# CalcSchematic.net
KiCad netlist of a schematic drawn in EAGLE
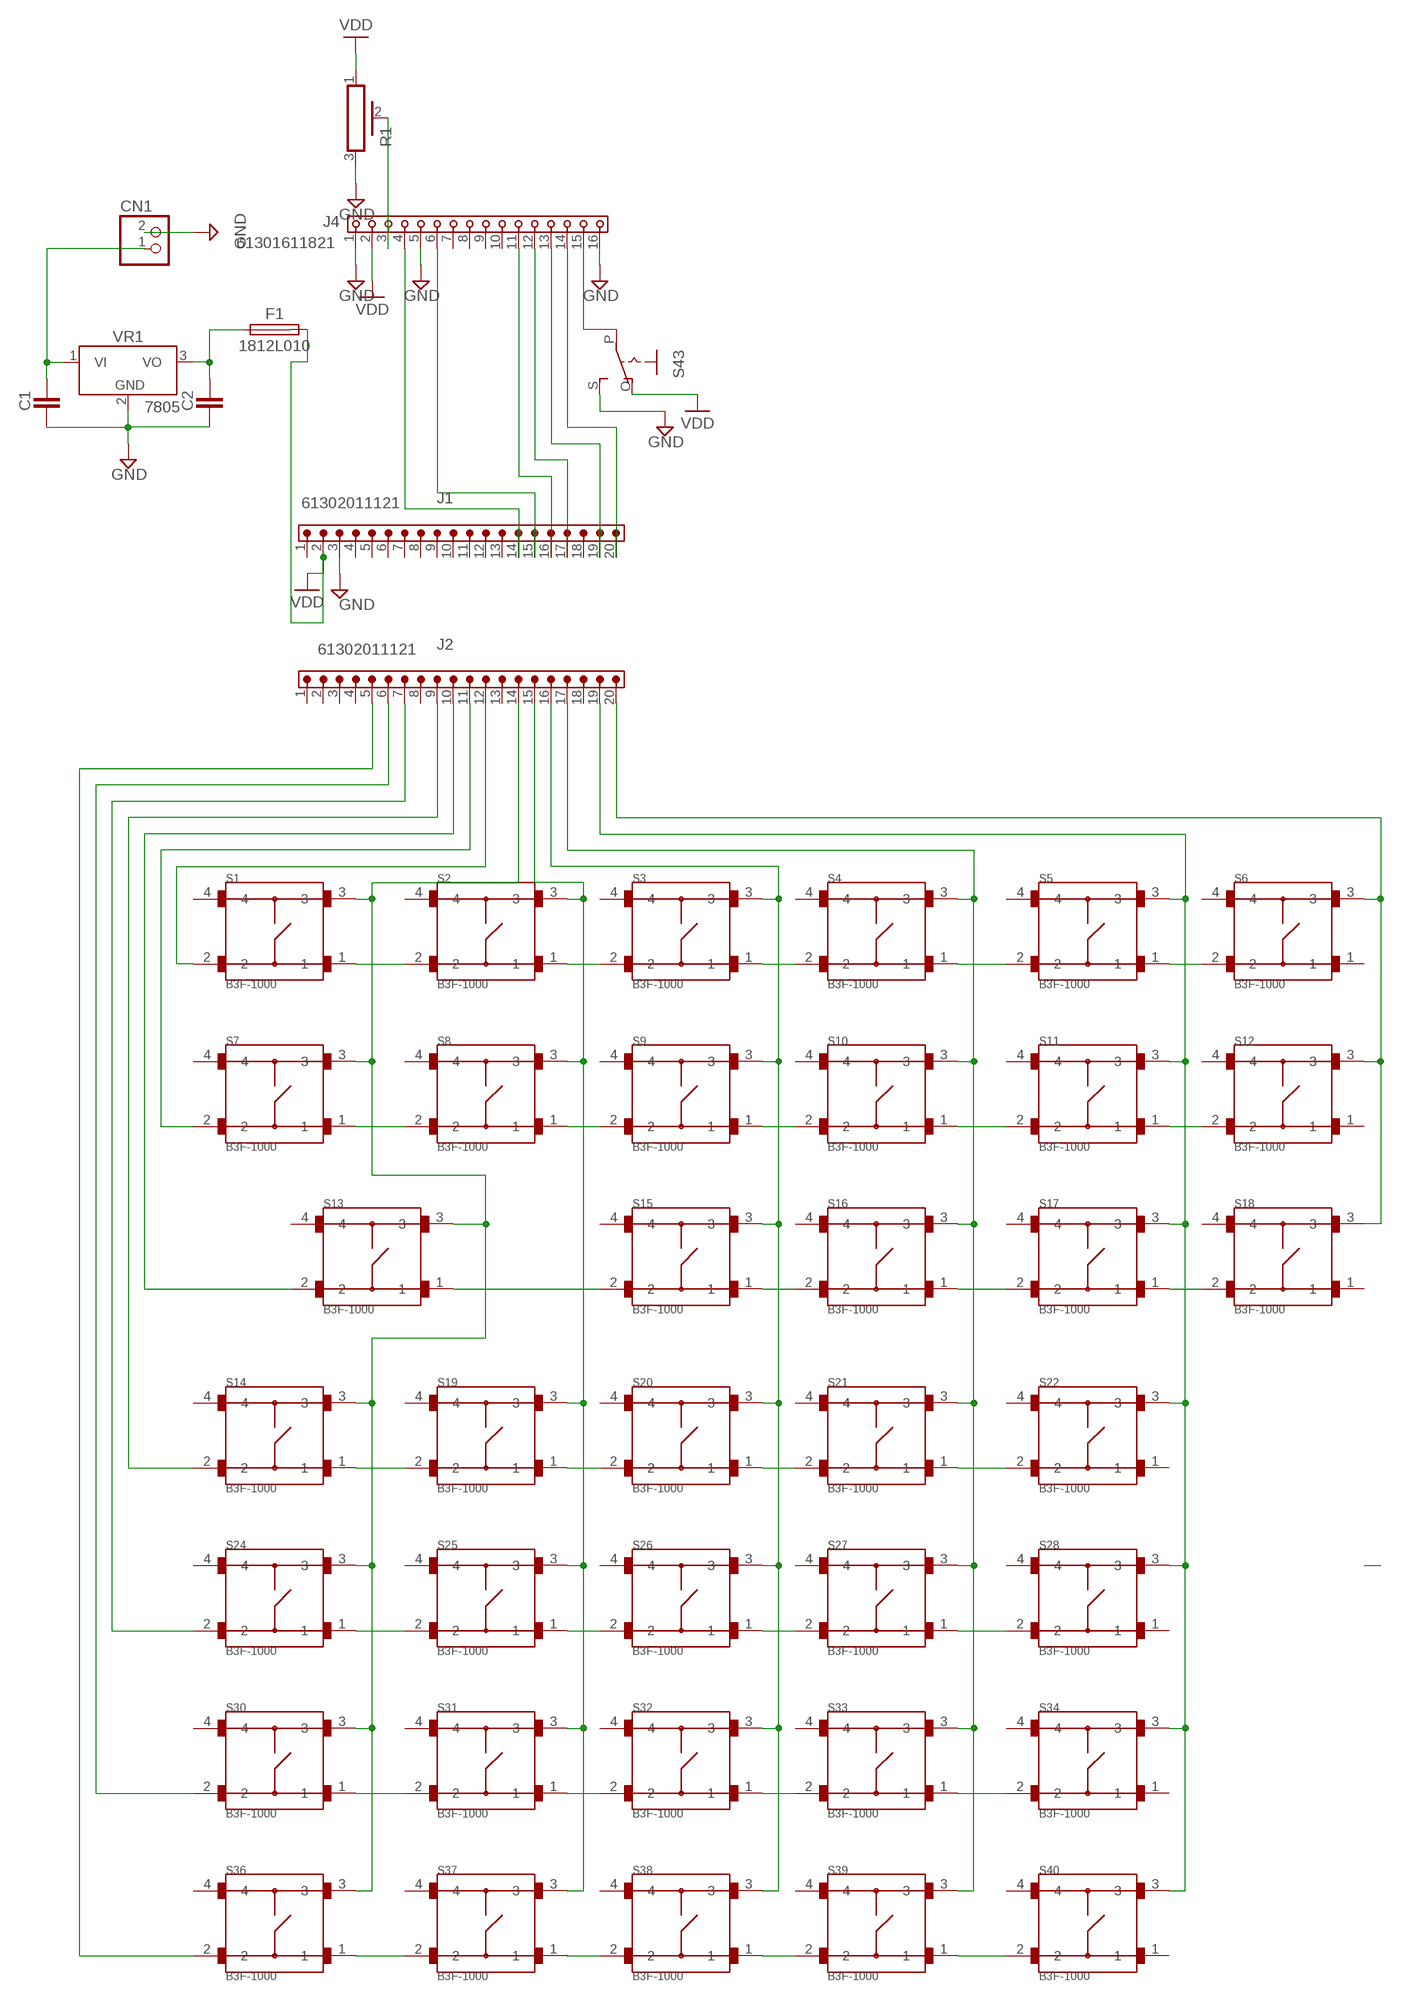
[diagram p0: schematic, sheet 1]

(export (version "E")
  (design (tool "Eeschema 10.0.6"))
  (components
    (comp (ref "C1")
      (value "CAPACITOR_CHIP-1206(3216-METRIC)")
      (footprint "eagle-import:CAPC3216X135")
      (libsource (lib "eagle-import") (part "CAPACITORCHIP-1206(3216-METRIC)_"))
    )
    (comp (ref "C2")
      (value "CAPACITOR_CHIP-1206(3216-METRIC)")
      (footprint "eagle-import:CAPC3216X135")
      (libsource (lib "eagle-import") (part "CAPACITORCHIP-1206(3216-METRIC)_"))
    )
    (comp (ref "CN1")
      (value "JST_2PIN-THM")
      (footprint "eagle-import:JST-PH-2-THM")
      (libsource (lib "eagle-import") (part "JST_2PIN-THM"))
    )
    (comp (ref "F1")
      (value "1812L010")
      (footprint "eagle-import:FUSC4532X125")
      (fields (field (name "MANUFACTURER") "Littlefuse"))
      (libsource (lib "eagle-import") (part "1812L010"))
    )
    (comp (ref "J1")
      (value "61302011121")
      (footprint "eagle-import:61302011121")
      (libsource (lib "eagle-import") (part "6130XX11121_61302011121"))
    )
    (comp (ref "J2")
      (value "61302011121")
      (footprint "eagle-import:61302011121")
      (libsource (lib "eagle-import") (part "6130XX11121_61302011121"))
    )
    (comp (ref "J4")
      (value "61301611821")
      (footprint "eagle-import:61301611821")
      (libsource (lib "eagle-import") (part "6130XX11821_61301611821"))
    )
    (comp (ref "R1")
      (value "POT_PV36P")
      (footprint "eagle-import:PV36P")
      (fields (field (name "MANUFACTURER") "BOURNS") (field (name "MPN") "PV36P"))
      (libsource (lib "eagle-import") (part "POT_PV36P"))
    )
    (comp (ref "S1")
      (value "B3F-1000")
      (footprint "eagle-import:SW_B3F-1000")
      (fields (field (name "MF") "Omron"))
      (libsource (lib "eagle-import") (part "B3F-1000"))
    )
    (comp (ref "S2")
      (value "B3F-1000")
      (footprint "eagle-import:SW_B3F-1000")
      (fields (field (name "MF") "Omron"))
      (libsource (lib "eagle-import") (part "B3F-1000"))
    )
    (comp (ref "S3")
      (value "B3F-1000")
      (footprint "eagle-import:SW_B3F-1000")
      (fields (field (name "MF") "Omron"))
      (libsource (lib "eagle-import") (part "B3F-1000"))
    )
    (comp (ref "S4")
      (value "B3F-1000")
      (footprint "eagle-import:SW_B3F-1000")
      (fields (field (name "MF") "Omron"))
      (libsource (lib "eagle-import") (part "B3F-1000"))
    )
    (comp (ref "S5")
      (value "B3F-1000")
      (footprint "eagle-import:SW_B3F-1000")
      (fields (field (name "MF") "Omron"))
      (libsource (lib "eagle-import") (part "B3F-1000"))
    )
    (comp (ref "S6")
      (value "B3F-1000")
      (footprint "eagle-import:SW_B3F-1000")
      (fields (field (name "MF") "Omron"))
      (libsource (lib "eagle-import") (part "B3F-1000"))
    )
    (comp (ref "S7")
      (value "B3F-1000")
      (footprint "eagle-import:SW_B3F-1000")
      (fields (field (name "MF") "Omron"))
      (libsource (lib "eagle-import") (part "B3F-1000"))
    )
    (comp (ref "S8")
      (value "B3F-1000")
      (footprint "eagle-import:SW_B3F-1000")
      (fields (field (name "MF") "Omron"))
      (libsource (lib "eagle-import") (part "B3F-1000"))
    )
    (comp (ref "S9")
      (value "B3F-1000")
      (footprint "eagle-import:SW_B3F-1000")
      (fields (field (name "MF") "Omron"))
      (libsource (lib "eagle-import") (part "B3F-1000"))
    )
    (comp (ref "S10")
      (value "B3F-1000")
      (footprint "eagle-import:SW_B3F-1000")
      (fields (field (name "MF") "Omron"))
      (libsource (lib "eagle-import") (part "B3F-1000"))
    )
    (comp (ref "S11")
      (value "B3F-1000")
      (footprint "eagle-import:SW_B3F-1000")
      (fields (field (name "MF") "Omron"))
      (libsource (lib "eagle-import") (part "B3F-1000"))
    )
    (comp (ref "S12")
      (value "B3F-1000")
      (footprint "eagle-import:SW_B3F-1000")
      (fields (field (name "MF") "Omron"))
      (libsource (lib "eagle-import") (part "B3F-1000"))
    )
    (comp (ref "S13")
      (value "B3F-1000")
      (footprint "eagle-import:SW_B3F-1000")
      (fields (field (name "MF") "Omron"))
      (libsource (lib "eagle-import") (part "B3F-1000"))
    )
    (comp (ref "S14")
      (value "B3F-1000")
      (footprint "eagle-import:SW_B3F-1000")
      (fields (field (name "MF") "Omron"))
      (libsource (lib "eagle-import") (part "B3F-1000"))
    )
    (comp (ref "S15")
      (value "B3F-1000")
      (footprint "eagle-import:SW_B3F-1000")
      (fields (field (name "MF") "Omron"))
      (libsource (lib "eagle-import") (part "B3F-1000"))
    )
    (comp (ref "S16")
      (value "B3F-1000")
      (footprint "eagle-import:SW_B3F-1000")
      (fields (field (name "MF") "Omron"))
      (libsource (lib "eagle-import") (part "B3F-1000"))
    )
    (comp (ref "S17")
      (value "B3F-1000")
      (footprint "eagle-import:SW_B3F-1000")
      (fields (field (name "MF") "Omron"))
      (libsource (lib "eagle-import") (part "B3F-1000"))
    )
    (comp (ref "S18")
      (value "B3F-1000")
      (footprint "eagle-import:SW_B3F-1000")
      (fields (field (name "MF") "Omron"))
      (libsource (lib "eagle-import") (part "B3F-1000"))
    )
    (comp (ref "S19")
      (value "B3F-1000")
      (footprint "eagle-import:SW_B3F-1000")
      (fields (field (name "MF") "Omron"))
      (libsource (lib "eagle-import") (part "B3F-1000"))
    )
    (comp (ref "S20")
      (value "B3F-1000")
      (footprint "eagle-import:SW_B3F-1000")
      (fields (field (name "MF") "Omron"))
      (libsource (lib "eagle-import") (part "B3F-1000"))
    )
    (comp (ref "S21")
      (value "B3F-1000")
      (footprint "eagle-import:SW_B3F-1000")
      (fields (field (name "MF") "Omron"))
      (libsource (lib "eagle-import") (part "B3F-1000"))
    )
    (comp (ref "S22")
      (value "B3F-1000")
      (footprint "eagle-import:SW_B3F-1000")
      (fields (field (name "MF") "Omron"))
      (libsource (lib "eagle-import") (part "B3F-1000"))
    )
    (comp (ref "S24")
      (value "B3F-1000")
      (footprint "eagle-import:SW_B3F-1000")
      (fields (field (name "MF") "Omron"))
      (libsource (lib "eagle-import") (part "B3F-1000"))
    )
    (comp (ref "S25")
      (value "B3F-1000")
      (footprint "eagle-import:SW_B3F-1000")
      (fields (field (name "MF") "Omron"))
      (libsource (lib "eagle-import") (part "B3F-1000"))
    )
    (comp (ref "S26")
      (value "B3F-1000")
      (footprint "eagle-import:SW_B3F-1000")
      (fields (field (name "MF") "Omron"))
      (libsource (lib "eagle-import") (part "B3F-1000"))
    )
    (comp (ref "S27")
      (value "B3F-1000")
      (footprint "eagle-import:SW_B3F-1000")
      (fields (field (name "MF") "Omron"))
      (libsource (lib "eagle-import") (part "B3F-1000"))
    )
    (comp (ref "S28")
      (value "B3F-1000")
      (footprint "eagle-import:SW_B3F-1000")
      (fields (field (name "MF") "Omron"))
      (libsource (lib "eagle-import") (part "B3F-1000"))
    )
    (comp (ref "S30")
      (value "B3F-1000")
      (footprint "eagle-import:SW_B3F-1000")
      (fields (field (name "MF") "Omron"))
      (libsource (lib "eagle-import") (part "B3F-1000"))
    )
    (comp (ref "S31")
      (value "B3F-1000")
      (footprint "eagle-import:SW_B3F-1000")
      (fields (field (name "MF") "Omron"))
      (libsource (lib "eagle-import") (part "B3F-1000"))
    )
    (comp (ref "S32")
      (value "B3F-1000")
      (footprint "eagle-import:SW_B3F-1000")
      (fields (field (name "MF") "Omron"))
      (libsource (lib "eagle-import") (part "B3F-1000"))
    )
    (comp (ref "S33")
      (value "B3F-1000")
      (footprint "eagle-import:SW_B3F-1000")
      (fields (field (name "MF") "Omron"))
      (libsource (lib "eagle-import") (part "B3F-1000"))
    )
    (comp (ref "S34")
      (value "B3F-1000")
      (footprint "eagle-import:SW_B3F-1000")
      (fields (field (name "MF") "Omron"))
      (libsource (lib "eagle-import") (part "B3F-1000"))
    )
    (comp (ref "S36")
      (value "B3F-1000")
      (footprint "eagle-import:SW_B3F-1000")
      (fields (field (name "MF") "Omron"))
      (libsource (lib "eagle-import") (part "B3F-1000"))
    )
    (comp (ref "S37")
      (value "B3F-1000")
      (footprint "eagle-import:SW_B3F-1000")
      (fields (field (name "MF") "Omron"))
      (libsource (lib "eagle-import") (part "B3F-1000"))
    )
    (comp (ref "S38")
      (value "B3F-1000")
      (footprint "eagle-import:SW_B3F-1000")
      (fields (field (name "MF") "Omron"))
      (libsource (lib "eagle-import") (part "B3F-1000"))
    )
    (comp (ref "S39")
      (value "B3F-1000")
      (footprint "eagle-import:SW_B3F-1000")
      (fields (field (name "MF") "Omron"))
      (libsource (lib "eagle-import") (part "B3F-1000"))
    )
    (comp (ref "S40")
      (value "B3F-1000")
      (footprint "eagle-import:SW_B3F-1000")
      (fields (field (name "MF") "Omron"))
      (libsource (lib "eagle-import") (part "B3F-1000"))
    )
    (comp (ref "S43")
      (value "EG1218S")
      (footprint "eagle-import:EG1218")
      (libsource (lib "eagle-import") (part "EG1218S"))
    )
    (comp (ref "VR1")
      (value "7805")
      (footprint "eagle-import:TO220V")
      (fields (field (name "MANUFACTURER") "Generic"))
      (libsource (lib "eagle-import") (part "LM7805_TO220V"))
    )
  )
  (nets
    (net (code "1") (name "GND") (class "Default")
      (node (ref "C1") (pin "2") (pinfunction "2_2") (pintype "passive"))
      (node (ref "C2") (pin "2") (pinfunction "2_2") (pintype "passive"))
      (node (ref "CN1") (pin "2") (pinfunction "1_2") (pintype "passive"))
      (node (ref "J1") (pin "3") (pinfunction "3_3") (pintype "passive"))
      (node (ref "J4") (pin "1") (pinfunction "1_1") (pintype "passive"))
      (node (ref "J4") (pin "16") (pinfunction "16_16") (pintype "passive"))
      (node (ref "J4") (pin "5") (pinfunction "5_5") (pintype "passive"))
      (node (ref "R1") (pin "3") (pinfunction "P$3_3") (pintype "passive"))
      (node (ref "S43") (pin "S") (pinfunction "S_S") (pintype "passive"))
      (node (ref "VR1") (pin "2") (pinfunction "GND_2") (pintype "passive"))
    )
    (net (code "2") (name "Net-(CN1-2)") (class "Default")
      (node (ref "C1") (pin "1") (pinfunction "1_1") (pintype "passive"))
      (node (ref "CN1") (pin "1") (pinfunction "2_1") (pintype "passive"))
      (node (ref "VR1") (pin "1") (pinfunction "VI_1") (pintype "input"))
    )
    (net (code "3") (name "Net-(J1-Pad14)") (class "Default")
      (node (ref "J1") (pin "14") (pinfunction "14_14") (pintype "passive"))
      (node (ref "J4") (pin "4") (pinfunction "4_4") (pintype "passive"))
    )
    (net (code "4") (name "Net-(J1-Pad15)") (class "Default")
      (node (ref "J1") (pin "15") (pinfunction "15_15") (pintype "passive"))
      (node (ref "J4") (pin "6") (pinfunction "6_6") (pintype "passive"))
    )
    (net (code "5") (name "Net-(J1-Pad16)") (class "Default")
      (node (ref "J1") (pin "16") (pinfunction "16_16") (pintype "passive"))
      (node (ref "J4") (pin "11") (pinfunction "11_11") (pintype "passive"))
    )
    (net (code "6") (name "Net-(J1-Pad17)") (class "Default")
      (node (ref "J1") (pin "17") (pinfunction "17_17") (pintype "passive"))
      (node (ref "J4") (pin "12") (pinfunction "12_12") (pintype "passive"))
    )
    (net (code "7") (name "Net-(J1-Pad19)") (class "Default")
      (node (ref "J1") (pin "19") (pinfunction "19_19") (pintype "passive"))
      (node (ref "J4") (pin "13") (pinfunction "13_13") (pintype "passive"))
    )
    (net (code "8") (name "Net-(J1-Pad20)") (class "Default")
      (node (ref "J1") (pin "20") (pinfunction "20_20") (pintype "passive"))
      (node (ref "J4") (pin "14") (pinfunction "14_14") (pintype "passive"))
    )
    (net (code "9") (name "Net-(J2-Pad5)") (class "Default")
      (node (ref "J2") (pin "5") (pinfunction "5_5") (pintype "passive"))
      (node (ref "S36") (pin "2") (pinfunction "2_2") (pintype "passive"))
    )
    (net (code "10") (name "Net-(J2-Pad6)") (class "Default")
      (node (ref "J2") (pin "6") (pinfunction "6_6") (pintype "passive"))
      (node (ref "S30") (pin "2") (pinfunction "2_2") (pintype "passive"))
    )
    (net (code "11") (name "Net-(J2-Pad7)") (class "Default")
      (node (ref "J2") (pin "7") (pinfunction "7_7") (pintype "passive"))
      (node (ref "S24") (pin "2") (pinfunction "2_2") (pintype "passive"))
    )
    (net (code "12") (name "Net-(J2-Pad9)") (class "Default")
      (node (ref "J2") (pin "9") (pinfunction "9_9") (pintype "passive"))
      (node (ref "S14") (pin "2") (pinfunction "2_2") (pintype "passive"))
    )
    (net (code "13") (name "Net-(J2-Pad10)") (class "Default")
      (node (ref "J2") (pin "10") (pinfunction "10_10") (pintype "passive"))
      (node (ref "S13") (pin "2") (pinfunction "2_2") (pintype "passive"))
    )
    (net (code "14") (name "Net-(J2-Pad11)") (class "Default")
      (node (ref "J2") (pin "11") (pinfunction "11_11") (pintype "passive"))
      (node (ref "S7") (pin "2") (pinfunction "2_2") (pintype "passive"))
    )
    (net (code "15") (name "Net-(J2-Pad12)") (class "Default")
      (node (ref "J2") (pin "12") (pinfunction "12_12") (pintype "passive"))
      (node (ref "S1") (pin "2") (pinfunction "2_2") (pintype "passive"))
    )
    (net (code "16") (name "Net-(J2-Pad14)") (class "Default")
      (node (ref "J2") (pin "14") (pinfunction "14_14") (pintype "passive"))
      (node (ref "S1") (pin "3") (pinfunction "3_3") (pintype "passive"))
      (node (ref "S13") (pin "3") (pinfunction "3_3") (pintype "passive"))
      (node (ref "S14") (pin "3") (pinfunction "3_3") (pintype "passive"))
      (node (ref "S24") (pin "3") (pinfunction "3_3") (pintype "passive"))
      (node (ref "S30") (pin "3") (pinfunction "3_3") (pintype "passive"))
      (node (ref "S36") (pin "3") (pinfunction "3_3") (pintype "passive"))
      (node (ref "S7") (pin "3") (pinfunction "3_3") (pintype "passive"))
    )
    (net (code "17") (name "Net-(J2-Pad15)") (class "Default")
      (node (ref "J2") (pin "15") (pinfunction "15_15") (pintype "passive"))
      (node (ref "S19") (pin "3") (pinfunction "3_3") (pintype "passive"))
      (node (ref "S2") (pin "3") (pinfunction "3_3") (pintype "passive"))
      (node (ref "S25") (pin "3") (pinfunction "3_3") (pintype "passive"))
      (node (ref "S31") (pin "3") (pinfunction "3_3") (pintype "passive"))
      (node (ref "S37") (pin "3") (pinfunction "3_3") (pintype "passive"))
      (node (ref "S8") (pin "3") (pinfunction "3_3") (pintype "passive"))
    )
    (net (code "18") (name "Net-(J2-Pad16)") (class "Default")
      (node (ref "J2") (pin "16") (pinfunction "16_16") (pintype "passive"))
      (node (ref "S15") (pin "3") (pinfunction "3_3") (pintype "passive"))
      (node (ref "S20") (pin "3") (pinfunction "3_3") (pintype "passive"))
      (node (ref "S26") (pin "3") (pinfunction "3_3") (pintype "passive"))
      (node (ref "S3") (pin "3") (pinfunction "3_3") (pintype "passive"))
      (node (ref "S32") (pin "3") (pinfunction "3_3") (pintype "passive"))
      (node (ref "S38") (pin "3") (pinfunction "3_3") (pintype "passive"))
      (node (ref "S9") (pin "3") (pinfunction "3_3") (pintype "passive"))
    )
    (net (code "19") (name "Net-(J2-Pad17)") (class "Default")
      (node (ref "J2") (pin "17") (pinfunction "17_17") (pintype "passive"))
      (node (ref "S10") (pin "3") (pinfunction "3_3") (pintype "passive"))
      (node (ref "S16") (pin "3") (pinfunction "3_3") (pintype "passive"))
      (node (ref "S21") (pin "3") (pinfunction "3_3") (pintype "passive"))
      (node (ref "S27") (pin "3") (pinfunction "3_3") (pintype "passive"))
      (node (ref "S33") (pin "3") (pinfunction "3_3") (pintype "passive"))
      (node (ref "S39") (pin "3") (pinfunction "3_3") (pintype "passive"))
      (node (ref "S4") (pin "3") (pinfunction "3_3") (pintype "passive"))
    )
    (net (code "20") (name "Net-(J2-Pad19)") (class "Default")
      (node (ref "J2") (pin "19") (pinfunction "19_19") (pintype "passive"))
      (node (ref "S11") (pin "3") (pinfunction "3_3") (pintype "passive"))
      (node (ref "S17") (pin "3") (pinfunction "3_3") (pintype "passive"))
      (node (ref "S22") (pin "3") (pinfunction "3_3") (pintype "passive"))
      (node (ref "S28") (pin "3") (pinfunction "3_3") (pintype "passive"))
      (node (ref "S34") (pin "3") (pinfunction "3_3") (pintype "passive"))
      (node (ref "S40") (pin "3") (pinfunction "3_3") (pintype "passive"))
      (node (ref "S5") (pin "3") (pinfunction "3_3") (pintype "passive"))
    )
    (net (code "21") (name "Net-(J2-Pad20)") (class "Default")
      (node (ref "J2") (pin "20") (pinfunction "20_20") (pintype "passive"))
      (node (ref "S12") (pin "3") (pinfunction "3_3") (pintype "passive"))
      (node (ref "S18") (pin "3") (pinfunction "3_3") (pintype "passive"))
      (node (ref "S6") (pin "3") (pinfunction "3_3") (pintype "passive"))
    )
    (net (code "22") (name "Net-(J4-Pad15)") (class "Default")
      (node (ref "J4") (pin "15") (pinfunction "15_15") (pintype "passive"))
      (node (ref "S43") (pin "P") (pinfunction "P_P") (pintype "passive"))
    )
    (net (code "23") (name "Net-(R1-P$2)") (class "Default")
      (node (ref "J4") (pin "3") (pinfunction "3_3") (pintype "passive"))
      (node (ref "R1") (pin "2") (pinfunction "P$2_2") (pintype "passive"))
    )
    (net (code "24") (name "Net-(S1-Pad1)") (class "Default")
      (node (ref "S1") (pin "1") (pinfunction "1_1") (pintype "passive"))
      (node (ref "S2") (pin "2") (pinfunction "2_2") (pintype "passive"))
    )
    (net (code "25") (name "Net-(S2-Pad1)") (class "Default")
      (node (ref "S2") (pin "1") (pinfunction "1_1") (pintype "passive"))
      (node (ref "S3") (pin "2") (pinfunction "2_2") (pintype "passive"))
    )
    (net (code "26") (name "Net-(S3-Pad1)") (class "Default")
      (node (ref "S3") (pin "1") (pinfunction "1_1") (pintype "passive"))
      (node (ref "S4") (pin "2") (pinfunction "2_2") (pintype "passive"))
    )
    (net (code "27") (name "Net-(S4-Pad1)") (class "Default")
      (node (ref "S4") (pin "1") (pinfunction "1_1") (pintype "passive"))
      (node (ref "S5") (pin "2") (pinfunction "2_2") (pintype "passive"))
    )
    (net (code "28") (name "Net-(S5-Pad1)") (class "Default")
      (node (ref "S5") (pin "1") (pinfunction "1_1") (pintype "passive"))
      (node (ref "S6") (pin "2") (pinfunction "2_2") (pintype "passive"))
    )
    (net (code "29") (name "Net-(S7-Pad1)") (class "Default")
      (node (ref "S7") (pin "1") (pinfunction "1_1") (pintype "passive"))
      (node (ref "S8") (pin "2") (pinfunction "2_2") (pintype "passive"))
    )
    (net (code "30") (name "Net-(S8-Pad1)") (class "Default")
      (node (ref "S8") (pin "1") (pinfunction "1_1") (pintype "passive"))
      (node (ref "S9") (pin "2") (pinfunction "2_2") (pintype "passive"))
    )
    (net (code "31") (name "Net-(S10-Pad1)") (class "Default")
      (node (ref "S10") (pin "1") (pinfunction "1_1") (pintype "passive"))
      (node (ref "S11") (pin "2") (pinfunction "2_2") (pintype "passive"))
    )
    (net (code "32") (name "Net-(S10-Pad2)") (class "Default")
      (node (ref "S10") (pin "2") (pinfunction "2_2") (pintype "passive"))
      (node (ref "S9") (pin "1") (pinfunction "1_1") (pintype "passive"))
    )
    (net (code "33") (name "Net-(S11-Pad1)") (class "Default")
      (node (ref "S11") (pin "1") (pinfunction "1_1") (pintype "passive"))
      (node (ref "S12") (pin "2") (pinfunction "2_2") (pintype "passive"))
    )
    (net (code "34") (name "Net-(S13-Pad1)") (class "Default")
      (node (ref "S13") (pin "1") (pinfunction "1_1") (pintype "passive"))
      (node (ref "S15") (pin "2") (pinfunction "2_2") (pintype "passive"))
    )
    (net (code "35") (name "Net-(S14-Pad1)") (class "Default")
      (node (ref "S14") (pin "1") (pinfunction "1_1") (pintype "passive"))
      (node (ref "S19") (pin "2") (pinfunction "2_2") (pintype "passive"))
    )
    (net (code "36") (name "Net-(S15-Pad1)") (class "Default")
      (node (ref "S15") (pin "1") (pinfunction "1_1") (pintype "passive"))
      (node (ref "S16") (pin "2") (pinfunction "2_2") (pintype "passive"))
    )
    (net (code "37") (name "Net-(S16-Pad1)") (class "Default")
      (node (ref "S16") (pin "1") (pinfunction "1_1") (pintype "passive"))
      (node (ref "S17") (pin "2") (pinfunction "2_2") (pintype "passive"))
    )
    (net (code "38") (name "Net-(S17-Pad1)") (class "Default")
      (node (ref "S17") (pin "1") (pinfunction "1_1") (pintype "passive"))
      (node (ref "S18") (pin "2") (pinfunction "2_2") (pintype "passive"))
    )
    (net (code "39") (name "Net-(S19-Pad1)") (class "Default")
      (node (ref "S19") (pin "1") (pinfunction "1_1") (pintype "passive"))
      (node (ref "S20") (pin "2") (pinfunction "2_2") (pintype "passive"))
    )
    (net (code "40") (name "Net-(S20-Pad1)") (class "Default")
      (node (ref "S20") (pin "1") (pinfunction "1_1") (pintype "passive"))
      (node (ref "S21") (pin "2") (pinfunction "2_2") (pintype "passive"))
    )
    (net (code "41") (name "Net-(S21-Pad1)") (class "Default")
      (node (ref "S21") (pin "1") (pinfunction "1_1") (pintype "passive"))
      (node (ref "S22") (pin "2") (pinfunction "2_2") (pintype "passive"))
    )
    (net (code "42") (name "Net-(S24-Pad1)") (class "Default")
      (node (ref "S24") (pin "1") (pinfunction "1_1") (pintype "passive"))
      (node (ref "S25") (pin "2") (pinfunction "2_2") (pintype "passive"))
    )
    (net (code "43") (name "Net-(S25-Pad1)") (class "Default")
      (node (ref "S25") (pin "1") (pinfunction "1_1") (pintype "passive"))
      (node (ref "S26") (pin "2") (pinfunction "2_2") (pintype "passive"))
    )
    (net (code "44") (name "Net-(S26-Pad1)") (class "Default")
      (node (ref "S26") (pin "1") (pinfunction "1_1") (pintype "passive"))
      (node (ref "S27") (pin "2") (pinfunction "2_2") (pintype "passive"))
    )
    (net (code "45") (name "Net-(S27-Pad1)") (class "Default")
      (node (ref "S27") (pin "1") (pinfunction "1_1") (pintype "passive"))
      (node (ref "S28") (pin "2") (pinfunction "2_2") (pintype "passive"))
    )
    (net (code "46") (name "Net-(S30-Pad1)") (class "Default")
      (node (ref "S30") (pin "1") (pinfunction "1_1") (pintype "passive"))
      (node (ref "S31") (pin "2") (pinfunction "2_2") (pintype "passive"))
    )
    (net (code "47") (name "Net-(S31-Pad1)") (class "Default")
      (node (ref "S31") (pin "1") (pinfunction "1_1") (pintype "passive"))
      (node (ref "S32") (pin "2") (pinfunction "2_2") (pintype "passive"))
    )
    (net (code "48") (name "Net-(S32-Pad1)") (class "Default")
      (node (ref "S32") (pin "1") (pinfunction "1_1") (pintype "passive"))
      (node (ref "S33") (pin "2") (pinfunction "2_2") (pintype "passive"))
    )
    (net (code "49") (name "Net-(S33-Pad1)") (class "Default")
      (node (ref "S33") (pin "1") (pinfunction "1_1") (pintype "passive"))
      (node (ref "S34") (pin "2") (pinfunction "2_2") (pintype "passive"))
    )
    (net (code "50") (name "Net-(S36-Pad1)") (class "Default")
      (node (ref "S36") (pin "1") (pinfunction "1_1") (pintype "passive"))
      (node (ref "S37") (pin "2") (pinfunction "2_2") (pintype "passive"))
    )
    (net (code "51") (name "Net-(S37-Pad1)") (class "Default")
      (node (ref "S37") (pin "1") (pinfunction "1_1") (pintype "passive"))
      (node (ref "S38") (pin "2") (pinfunction "2_2") (pintype "passive"))
    )
    (net (code "52") (name "Net-(S38-Pad1)") (class "Default")
      (node (ref "S38") (pin "1") (pinfunction "1_1") (pintype "passive"))
      (node (ref "S39") (pin "2") (pinfunction "2_2") (pintype "passive"))
    )
    (net (code "53") (name "Net-(S39-Pad1)") (class "Default")
      (node (ref "S39") (pin "1") (pinfunction "1_1") (pintype "passive"))
      (node (ref "S40") (pin "2") (pinfunction "2_2") (pintype "passive"))
    )
    (net (code "54") (name "Net-(VR1-VO)") (class "Default")
      (node (ref "C2") (pin "1") (pinfunction "1_1") (pintype "passive"))
      (node (ref "F1") (pin "1") (pinfunction "1_1") (pintype "passive"))
      (node (ref "VR1") (pin "3") (pinfunction "VO_3") (pintype "output"))
    )
    (net (code "55") (name "VDD") (class "Default")
      (node (ref "F1") (pin "2") (pinfunction "2_2") (pintype "passive"))
      (node (ref "J1") (pin "2") (pinfunction "2_2") (pintype "passive"))
      (node (ref "J4") (pin "2") (pinfunction "2_2") (pintype "passive"))
      (node (ref "R1") (pin "1") (pinfunction "P$1_1") (pintype "passive"))
      (node (ref "S43") (pin "O") (pinfunction "O_O") (pintype "passive"))
    )
    (net (code "56") (name "unconnected-(J1-Pad1)") (class "Default")
      (node (ref "J1") (pin "1") (pinfunction "1_1") (pintype "passive"))
    )
    (net (code "57") (name "unconnected-(J1-Pad4)") (class "Default")
      (node (ref "J1") (pin "4") (pinfunction "4_4") (pintype "passive"))
    )
    (net (code "58") (name "unconnected-(J1-Pad5)") (class "Default")
      (node (ref "J1") (pin "5") (pinfunction "5_5") (pintype "passive"))
    )
    (net (code "59") (name "unconnected-(J1-Pad6)") (class "Default")
      (node (ref "J1") (pin "6") (pinfunction "6_6") (pintype "passive"))
    )
    (net (code "60") (name "unconnected-(J1-Pad7)") (class "Default")
      (node (ref "J1") (pin "7") (pinfunction "7_7") (pintype "passive"))
    )
    (net (code "61") (name "unconnected-(J1-Pad8)") (class "Default")
      (node (ref "J1") (pin "8") (pinfunction "8_8") (pintype "passive"))
    )
    (net (code "62") (name "unconnected-(J1-Pad9)") (class "Default")
      (node (ref "J1") (pin "9") (pinfunction "9_9") (pintype "passive"))
    )
    (net (code "63") (name "unconnected-(J1-Pad10)") (class "Default")
      (node (ref "J1") (pin "10") (pinfunction "10_10") (pintype "passive"))
    )
    (net (code "64") (name "unconnected-(J1-Pad11)") (class "Default")
      (node (ref "J1") (pin "11") (pinfunction "11_11") (pintype "passive"))
    )
    (net (code "65") (name "unconnected-(J1-Pad12)") (class "Default")
      (node (ref "J1") (pin "12") (pinfunction "12_12") (pintype "passive"))
    )
    (net (code "66") (name "unconnected-(J1-Pad13)") (class "Default")
      (node (ref "J1") (pin "13") (pinfunction "13_13") (pintype "passive"))
    )
    (net (code "67") (name "unconnected-(J1-Pad18)") (class "Default")
      (node (ref "J1") (pin "18") (pinfunction "18_18") (pintype "passive"))
    )
    (net (code "68") (name "unconnected-(J2-Pad1)") (class "Default")
      (node (ref "J2") (pin "1") (pinfunction "1_1") (pintype "passive"))
    )
    (net (code "69") (name "unconnected-(J2-Pad2)") (class "Default")
      (node (ref "J2") (pin "2") (pinfunction "2_2") (pintype "passive"))
    )
    (net (code "70") (name "unconnected-(J2-Pad3)") (class "Default")
      (node (ref "J2") (pin "3") (pinfunction "3_3") (pintype "passive"))
    )
    (net (code "71") (name "unconnected-(J2-Pad4)") (class "Default")
      (node (ref "J2") (pin "4") (pinfunction "4_4") (pintype "passive"))
    )
    (net (code "72") (name "unconnected-(J2-Pad8)") (class "Default")
      (node (ref "J2") (pin "8") (pinfunction "8_8") (pintype "passive"))
    )
    (net (code "73") (name "unconnected-(J2-Pad13)") (class "Default")
      (node (ref "J2") (pin "13") (pinfunction "13_13") (pintype "passive"))
    )
    (net (code "74") (name "unconnected-(J2-Pad18)") (class "Default")
      (node (ref "J2") (pin "18") (pinfunction "18_18") (pintype "passive"))
    )
    (net (code "75") (name "unconnected-(J4-Pad7)") (class "Default")
      (node (ref "J4") (pin "7") (pinfunction "7_7") (pintype "passive"))
    )
    (net (code "76") (name "unconnected-(J4-Pad8)") (class "Default")
      (node (ref "J4") (pin "8") (pinfunction "8_8") (pintype "passive"))
    )
    (net (code "77") (name "unconnected-(J4-Pad9)") (class "Default")
      (node (ref "J4") (pin "9") (pinfunction "9_9") (pintype "passive"))
    )
    (net (code "78") (name "unconnected-(J4-Pad10)") (class "Default")
      (node (ref "J4") (pin "10") (pinfunction "10_10") (pintype "passive"))
    )
    (net (code "79") (name "unconnected-(S1-Pad4)") (class "Default")
      (node (ref "S1") (pin "4") (pinfunction "4_4") (pintype "passive"))
    )
    (net (code "80") (name "unconnected-(S2-Pad4)") (class "Default")
      (node (ref "S2") (pin "4") (pinfunction "4_4") (pintype "passive"))
    )
    (net (code "81") (name "unconnected-(S3-Pad4)") (class "Default")
      (node (ref "S3") (pin "4") (pinfunction "4_4") (pintype "passive"))
    )
    (net (code "82") (name "unconnected-(S4-Pad4)") (class "Default")
      (node (ref "S4") (pin "4") (pinfunction "4_4") (pintype "passive"))
    )
    (net (code "83") (name "unconnected-(S5-Pad4)") (class "Default")
      (node (ref "S5") (pin "4") (pinfunction "4_4") (pintype "passive"))
    )
    (net (code "84") (name "unconnected-(S6-Pad1)") (class "Default")
      (node (ref "S6") (pin "1") (pinfunction "1_1") (pintype "passive"))
    )
    (net (code "85") (name "unconnected-(S6-Pad4)") (class "Default")
      (node (ref "S6") (pin "4") (pinfunction "4_4") (pintype "passive"))
    )
    (net (code "86") (name "unconnected-(S7-Pad4)") (class "Default")
      (node (ref "S7") (pin "4") (pinfunction "4_4") (pintype "passive"))
    )
    (net (code "87") (name "unconnected-(S8-Pad4)") (class "Default")
      (node (ref "S8") (pin "4") (pinfunction "4_4") (pintype "passive"))
    )
    (net (code "88") (name "unconnected-(S9-Pad4)") (class "Default")
      (node (ref "S9") (pin "4") (pinfunction "4_4") (pintype "passive"))
    )
    (net (code "89") (name "unconnected-(S10-Pad4)") (class "Default")
      (node (ref "S10") (pin "4") (pinfunction "4_4") (pintype "passive"))
    )
    (net (code "90") (name "unconnected-(S11-Pad4)") (class "Default")
      (node (ref "S11") (pin "4") (pinfunction "4_4") (pintype "passive"))
    )
    (net (code "91") (name "unconnected-(S12-Pad1)") (class "Default")
      (node (ref "S12") (pin "1") (pinfunction "1_1") (pintype "passive"))
    )
    (net (code "92") (name "unconnected-(S12-Pad4)") (class "Default")
      (node (ref "S12") (pin "4") (pinfunction "4_4") (pintype "passive"))
    )
    (net (code "93") (name "unconnected-(S13-Pad4)") (class "Default")
      (node (ref "S13") (pin "4") (pinfunction "4_4") (pintype "passive"))
    )
    (net (code "94") (name "unconnected-(S14-Pad4)") (class "Default")
      (node (ref "S14") (pin "4") (pinfunction "4_4") (pintype "passive"))
    )
    (net (code "95") (name "unconnected-(S15-Pad4)") (class "Default")
      (node (ref "S15") (pin "4") (pinfunction "4_4") (pintype "passive"))
    )
    (net (code "96") (name "unconnected-(S16-Pad4)") (class "Default")
      (node (ref "S16") (pin "4") (pinfunction "4_4") (pintype "passive"))
    )
    (net (code "97") (name "unconnected-(S17-Pad4)") (class "Default")
      (node (ref "S17") (pin "4") (pinfunction "4_4") (pintype "passive"))
    )
    (net (code "98") (name "unconnected-(S18-Pad1)") (class "Default")
      (node (ref "S18") (pin "1") (pinfunction "1_1") (pintype "passive"))
    )
    (net (code "99") (name "unconnected-(S18-Pad4)") (class "Default")
      (node (ref "S18") (pin "4") (pinfunction "4_4") (pintype "passive"))
    )
    (net (code "100") (name "unconnected-(S19-Pad4)") (class "Default")
      (node (ref "S19") (pin "4") (pinfunction "4_4") (pintype "passive"))
    )
    (net (code "101") (name "unconnected-(S20-Pad4)") (class "Default")
      (node (ref "S20") (pin "4") (pinfunction "4_4") (pintype "passive"))
    )
    (net (code "102") (name "unconnected-(S21-Pad4)") (class "Default")
      (node (ref "S21") (pin "4") (pinfunction "4_4") (pintype "passive"))
    )
    (net (code "103") (name "unconnected-(S22-Pad1)") (class "Default")
      (node (ref "S22") (pin "1") (pinfunction "1_1") (pintype "passive"))
    )
    (net (code "104") (name "unconnected-(S22-Pad4)") (class "Default")
      (node (ref "S22") (pin "4") (pinfunction "4_4") (pintype "passive"))
    )
    (net (code "105") (name "unconnected-(S24-Pad4)") (class "Default")
      (node (ref "S24") (pin "4") (pinfunction "4_4") (pintype "passive"))
    )
    (net (code "106") (name "unconnected-(S25-Pad4)") (class "Default")
      (node (ref "S25") (pin "4") (pinfunction "4_4") (pintype "passive"))
    )
    (net (code "107") (name "unconnected-(S26-Pad4)") (class "Default")
      (node (ref "S26") (pin "4") (pinfunction "4_4") (pintype "passive"))
    )
    (net (code "108") (name "unconnected-(S27-Pad4)") (class "Default")
      (node (ref "S27") (pin "4") (pinfunction "4_4") (pintype "passive"))
    )
    (net (code "109") (name "unconnected-(S28-Pad1)") (class "Default")
      (node (ref "S28") (pin "1") (pinfunction "1_1") (pintype "passive"))
    )
    (net (code "110") (name "unconnected-(S28-Pad4)") (class "Default")
      (node (ref "S28") (pin "4") (pinfunction "4_4") (pintype "passive"))
    )
    (net (code "111") (name "unconnected-(S30-Pad4)") (class "Default")
      (node (ref "S30") (pin "4") (pinfunction "4_4") (pintype "passive"))
    )
    (net (code "112") (name "unconnected-(S31-Pad4)") (class "Default")
      (node (ref "S31") (pin "4") (pinfunction "4_4") (pintype "passive"))
    )
    (net (code "113") (name "unconnected-(S32-Pad4)") (class "Default")
      (node (ref "S32") (pin "4") (pinfunction "4_4") (pintype "passive"))
    )
    (net (code "114") (name "unconnected-(S33-Pad4)") (class "Default")
      (node (ref "S33") (pin "4") (pinfunction "4_4") (pintype "passive"))
    )
    (net (code "115") (name "unconnected-(S34-Pad1)") (class "Default")
      (node (ref "S34") (pin "1") (pinfunction "1_1") (pintype "passive"))
    )
    (net (code "116") (name "unconnected-(S34-Pad4)") (class "Default")
      (node (ref "S34") (pin "4") (pinfunction "4_4") (pintype "passive"))
    )
    (net (code "117") (name "unconnected-(S36-Pad4)") (class "Default")
      (node (ref "S36") (pin "4") (pinfunction "4_4") (pintype "passive"))
    )
    (net (code "118") (name "unconnected-(S37-Pad4)") (class "Default")
      (node (ref "S37") (pin "4") (pinfunction "4_4") (pintype "passive"))
    )
    (net (code "119") (name "unconnected-(S38-Pad4)") (class "Default")
      (node (ref "S38") (pin "4") (pinfunction "4_4") (pintype "passive"))
    )
    (net (code "120") (name "unconnected-(S39-Pad4)") (class "Default")
      (node (ref "S39") (pin "4") (pinfunction "4_4") (pintype "passive"))
    )
    (net (code "121") (name "unconnected-(S40-Pad1)") (class "Default")
      (node (ref "S40") (pin "1") (pinfunction "1_1") (pintype "passive"))
    )
    (net (code "122") (name "unconnected-(S40-Pad4)") (class "Default")
      (node (ref "S40") (pin "4") (pinfunction "4_4") (pintype "passive"))
    )
  )
)
